# CH340G_USB_TO_SERIAL_MODULE.net
KiCad netlist of a schematic drawn in Altium Designer
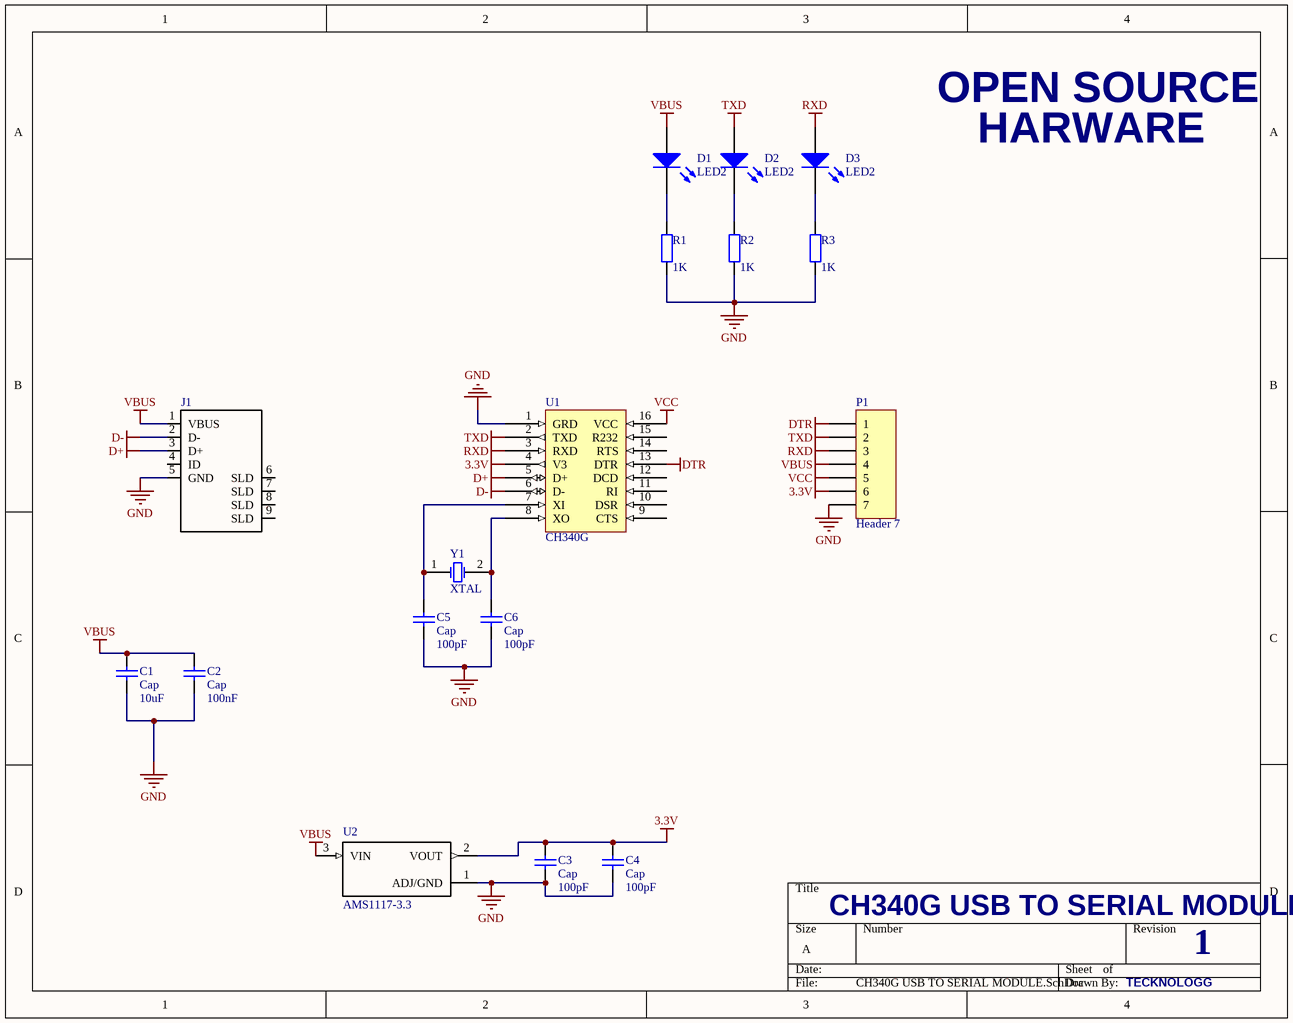
[diagram p0: CH340G USB TO SERIAL MODULE.SchDoc]

(export (version "E")
  (design (tool "Eeschema 10.0.6"))
  (components
    (comp (ref "C1")
      (value "Cap")
      (footprint "RAD-0.3")
      (description "Capacitor")
      (fields (field (name "ALTIUM_VALUE") "10uF") (field (name "PUBLISHER") "Altium Limited"))
      (libsource (lib "Miscellaneous Devices") (part "Cap"))
    )
    (comp (ref "C2")
      (value "Cap")
      (footprint "RAD-0.3")
      (description "Capacitor")
      (fields (field (name "ALTIUM_VALUE") "100nF") (field (name "PUBLISHER") "Altium Limited"))
      (libsource (lib "Miscellaneous Devices") (part "Cap"))
    )
    (comp (ref "C3")
      (value "Cap")
      (footprint "RAD-0.3")
      (description "Capacitor")
      (fields (field (name "ALTIUM_VALUE") "100pF") (field (name "PUBLISHER") "Altium Limited"))
      (libsource (lib "Miscellaneous Devices") (part "Cap"))
    )
    (comp (ref "C4")
      (value "Cap")
      (footprint "RAD-0.3")
      (description "Capacitor")
      (fields (field (name "ALTIUM_VALUE") "100pF") (field (name "PUBLISHER") "Altium Limited"))
      (libsource (lib "Miscellaneous Devices") (part "Cap"))
    )
    (comp (ref "C5")
      (value "Cap")
      (footprint "RAD-0.3")
      (description "Capacitor")
      (fields (field (name "ALTIUM_VALUE") "100pF") (field (name "PUBLISHER") "Altium Limited"))
      (libsource (lib "Miscellaneous Devices") (part "Cap"))
    )
    (comp (ref "C6")
      (value "Cap")
      (footprint "RAD-0.3")
      (description "Capacitor")
      (fields (field (name "ALTIUM_VALUE") "100pF") (field (name "PUBLISHER") "Altium Limited"))
      (libsource (lib "Miscellaneous Devices") (part "Cap"))
    )
    (comp (ref "D1")
      (value "LED2")
      (footprint "3.2X1.6X1.1")
      (description "Typical RED, GREEN, YELLOW, AMBER GaAs LED")
      (fields (field (name "PUBLISHER") "Altium Limited"))
      (libsource (lib "Miscellaneous Devices") (part "LED2"))
    )
    (comp (ref "D2")
      (value "LED2")
      (footprint "3.2X1.6X1.1")
      (description "Typical RED, GREEN, YELLOW, AMBER GaAs LED")
      (fields (field (name "PUBLISHER") "Altium Limited"))
      (libsource (lib "Miscellaneous Devices") (part "LED2"))
    )
    (comp (ref "D3")
      (value "LED2")
      (footprint "3.2X1.6X1.1")
      (description "Typical RED, GREEN, YELLOW, AMBER GaAs LED")
      (fields (field (name "PUBLISHER") "Altium Limited"))
      (libsource (lib "Miscellaneous Devices") (part "LED2"))
    )
    (comp (ref "J1")
      (value "1734035-1")
      (footprint "*TE_1734035-1")
      (description "Mini USB,R/A,SMT,B Type,pbFree")
      (fields (field (name "MF") "TE Connectivity"))
      (libsource (lib "1734035-1") (part "1734035-1"))
    )
    (comp (ref "P1")
      (value "Header 7")
      (footprint "HDR1X7")
      (description "Header, 7-Pin")
      (fields (field (name "PUBLISHER") "Altium Limited"))
      (libsource (lib "Miscellaneous Connectors") (part "Header 7"))
    )
    (comp (ref "R1")
      (value "1K")
      (footprint "AXIAL-0.4")
      (description "Resistor")
      (fields (field (name "PUBLISHER") "Altium Limited"))
      (libsource (lib "Miscellaneous Devices") (part "Res2"))
    )
    (comp (ref "R2")
      (value "1K")
      (footprint "AXIAL-0.4")
      (description "Resistor")
      (fields (field (name "PUBLISHER") "Altium Limited"))
      (libsource (lib "") (part "Res2_1"))
    )
    (comp (ref "R3")
      (value "1K")
      (footprint "AXIAL-0.4")
      (description "Resistor")
      (fields (field (name "PUBLISHER") "Altium Limited"))
      (libsource (lib "") (part "Res2_1"))
    )
    (comp (ref "U1") (value "CH340G") (libsource (lib "CH340.Schlib1") (part "CH340G")))
    (comp (ref "U2")
      (value "AMS1117-3.3")
      (footprint "*SOT229P700X180-4N")
      (description "Sot223/Pkg 1-Amp 3.3-Volt Low Drop Out Voltage Regulatator")
      (fields (field (name "MF") "Advanced Monolithic Systems"))
      (libsource (lib "AMS1117-3.3") (part "AMS1117-3.3"))
    )
    (comp (ref "Y1")
      (value "XTAL")
      (footprint "R38")
      (description "Crystal Oscillator")
      (fields (field (name "PUBLISHER") "Altium Limited"))
      (libsource (lib "Miscellaneous Devices") (part "XTAL"))
    )
  )
  (nets
    (net (code "1") (name "3.3V") (class "Default")
      (node (ref "C3") (pin "2") (pinfunction "2_2") (pintype "passive"))
      (node (ref "C4") (pin "2") (pinfunction "2_2") (pintype "passive"))
      (node (ref "P1") (pin "6") (pinfunction "6_6") (pintype "passive"))
      (node (ref "U1") (pin "4") (pinfunction "V3_4") (pintype "output"))
      (node (ref "U2") (pin "2") (pinfunction "VOUT_2") (pintype "output"))
    )
    (net (code "2") (name "D+") (class "Default")
      (node (ref "J1") (pin "3") (pinfunction "D+_3") (pintype "bidirectional"))
      (node (ref "U1") (pin "5") (pinfunction "D+_5") (pintype "bidirectional"))
    )
    (net (code "3") (name "D-") (class "Default")
      (node (ref "J1") (pin "2") (pinfunction "D-_2") (pintype "bidirectional"))
      (node (ref "U1") (pin "6") (pinfunction "D-_6") (pintype "bidirectional"))
    )
    (net (code "4") (name "DTR") (class "Default")
      (node (ref "P1") (pin "1") (pinfunction "1_1") (pintype "passive"))
      (node (ref "U1") (pin "13") (pinfunction "DTR_13") (pintype "input"))
    )
    (net (code "5") (name "GND") (class "Default")
      (node (ref "C1") (pin "1") (pinfunction "1_1") (pintype "passive"))
      (node (ref "C2") (pin "1") (pinfunction "1_1") (pintype "passive"))
      (node (ref "C3") (pin "1") (pinfunction "1_1") (pintype "passive"))
      (node (ref "C4") (pin "1") (pinfunction "1_1") (pintype "passive"))
      (node (ref "C5") (pin "1") (pinfunction "1_1") (pintype "passive"))
      (node (ref "C6") (pin "1") (pinfunction "1_1") (pintype "passive"))
      (node (ref "J1") (pin "5") (pinfunction "GND_5") (pintype "power_in"))
      (node (ref "P1") (pin "7") (pinfunction "7_7") (pintype "passive"))
      (node (ref "R1") (pin "1") (pinfunction "1_1") (pintype "passive"))
      (node (ref "R2") (pin "2") (pinfunction "2_2") (pintype "passive"))
      (node (ref "R3") (pin "2") (pinfunction "2_2") (pintype "passive"))
      (node (ref "U1") (pin "1") (pinfunction "GRD_1") (pintype "input"))
      (node (ref "U2") (pin "1") (pinfunction "ADJ/GND_1") (pintype "power_in"))
    )
    (net (code "6") (name "Net-(D1-K)") (class "Default")
      (node (ref "D1") (pin "2") (pinfunction "K_2") (pintype "passive"))
      (node (ref "R1") (pin "2") (pinfunction "2_2") (pintype "passive"))
    )
    (net (code "7") (name "Net-(D2-K)") (class "Default")
      (node (ref "D2") (pin "2") (pinfunction "K_2") (pintype "passive"))
      (node (ref "R2") (pin "1") (pinfunction "1_1") (pintype "passive"))
    )
    (net (code "8") (name "Net-(D3-K)") (class "Default")
      (node (ref "D3") (pin "2") (pinfunction "K_2") (pintype "passive"))
      (node (ref "R3") (pin "1") (pinfunction "1_1") (pintype "passive"))
    )
    (net (code "9") (name "Net-(U1-XI)") (class "Default")
      (node (ref "C5") (pin "2") (pinfunction "2_2") (pintype "passive"))
      (node (ref "U1") (pin "7") (pinfunction "XI_7") (pintype "input"))
      (node (ref "Y1") (pin "1") (pinfunction "OSC1_1") (pintype "passive"))
    )
    (net (code "10") (name "Net-(U1-XO)") (class "Default")
      (node (ref "C6") (pin "2") (pinfunction "2_2") (pintype "passive"))
      (node (ref "U1") (pin "8") (pinfunction "XO_8") (pintype "input"))
      (node (ref "Y1") (pin "2") (pinfunction "OSC2_2") (pintype "passive"))
    )
    (net (code "11") (name "RXD") (class "Default")
      (node (ref "D3") (pin "1") (pinfunction "A_1") (pintype "passive"))
      (node (ref "P1") (pin "3") (pinfunction "3_3") (pintype "passive"))
      (node (ref "U1") (pin "3") (pinfunction "RXD_3") (pintype "input"))
    )
    (net (code "12") (name "TXD") (class "Default")
      (node (ref "D2") (pin "1") (pinfunction "A_1") (pintype "passive"))
      (node (ref "P1") (pin "2") (pinfunction "2_2") (pintype "passive"))
      (node (ref "U1") (pin "2") (pinfunction "TXD_2") (pintype "output"))
    )
    (net (code "13") (name "VBUS") (class "Default")
      (node (ref "C1") (pin "2") (pinfunction "2_2") (pintype "passive"))
      (node (ref "C2") (pin "2") (pinfunction "2_2") (pintype "passive"))
      (node (ref "D1") (pin "1") (pinfunction "A_1") (pintype "passive"))
      (node (ref "J1") (pin "1") (pinfunction "VBUS_1") (pintype "power_in"))
      (node (ref "P1") (pin "4") (pinfunction "4_4") (pintype "passive"))
      (node (ref "U2") (pin "3") (pinfunction "VIN_3") (pintype "input"))
    )
    (net (code "14") (name "VCC") (class "Default")
      (node (ref "P1") (pin "5") (pinfunction "5_5") (pintype "passive"))
      (node (ref "U1") (pin "16") (pinfunction "VCC_16") (pintype "input"))
    )
    (net (code "15") (name "unconnected-(J1-ID-Pad4)") (class "Default")
      (node (ref "J1") (pin "4") (pinfunction "ID_4") (pintype "bidirectional"))
    )
    (net (code "16") (name "unconnected-(J1-SLD-Pad6)") (class "Default")
      (node (ref "J1") (pin "6") (pinfunction "SLD_6") (pintype "passive"))
    )
    (net (code "17") (name "unconnected-(J1-SLD-Pad7)") (class "Default")
      (node (ref "J1") (pin "7") (pinfunction "SLD_7") (pintype "passive"))
    )
    (net (code "18") (name "unconnected-(J1-SLD-Pad8)") (class "Default")
      (node (ref "J1") (pin "8") (pinfunction "SLD_8") (pintype "passive"))
    )
    (net (code "19") (name "unconnected-(J1-SLD-Pad9)") (class "Default")
      (node (ref "J1") (pin "9") (pinfunction "SLD_9") (pintype "passive"))
    )
    (net (code "20") (name "unconnected-(U1-CTS-Pad9)") (class "Default")
      (node (ref "U1") (pin "9") (pinfunction "CTS_9") (pintype "input"))
    )
    (net (code "21") (name "unconnected-(U1-DCD-Pad12)") (class "Default")
      (node (ref "U1") (pin "12") (pinfunction "DCD_12") (pintype "input"))
    )
    (net (code "22") (name "unconnected-(U1-DSR-Pad10)") (class "Default")
      (node (ref "U1") (pin "10") (pinfunction "DSR_10") (pintype "input"))
    )
    (net (code "23") (name "unconnected-(U1-R232-Pad15)") (class "Default")
      (node (ref "U1") (pin "15") (pinfunction "R232_15") (pintype "input"))
    )
    (net (code "24") (name "unconnected-(U1-RI-Pad11)") (class "Default")
      (node (ref "U1") (pin "11") (pinfunction "RI_11") (pintype "input"))
    )
    (net (code "25") (name "unconnected-(U1-RTS-Pad14)") (class "Default")
      (node (ref "U1") (pin "14") (pinfunction "RTS_14") (pintype "input"))
    )
  )
)
